# Brandon_PCB_DogTag.net
KiCad netlist of a schematic drawn in Altium Designer
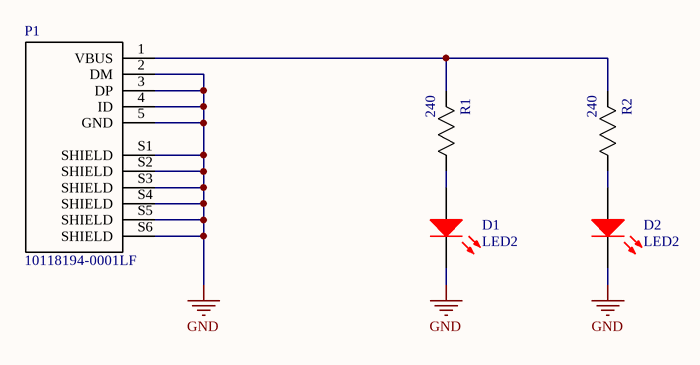
[diagram p0: Brandon PCB DogTag.SchDoc]

(export (version "E")
  (design (tool "Eeschema 10.0.6"))
  (components
    (comp (ref "D1")
      (value "LED2")
      (footprint "3.2X1.6X1.1")
      (description "Typical RED, GREEN, YELLOW, AMBER GaAs LED")
      (libsource (lib "AltiumLibraries") (part "LED RED SMD"))
    )
    (comp (ref "D2")
      (value "LED2")
      (footprint "3.2X1.6X1.1")
      (description "Typical RED, GREEN, YELLOW, AMBER GaAs LED")
      (libsource (lib "AltiumLibraries") (part "LED RED SMD"))
    )
    (comp (ref "P1")
      (value "10118194-0001LF")
      (footprint "USB Micro B Receptacle")
      (description "USB - micro B USB 2.0 Receptacle Connector 5 Position Surface Mount, Right Angle; Through Hole")
      (fields (field (name "MF") "Amphenol ICC (FCI)"))
      (libsource (lib "AltiumLibraries") (part "USB Micro B Receptacle"))
    )
    (comp (ref "R1")
      (value "240")
      (footprint "0805")
      (description "RES SMD 240 OHM 5% 1/8W 0805")
      (fields (field (name "TOLERANCE") "5%"))
      (libsource (lib "AltiumLibraries") (part "RES 240.0 1/8W"))
    )
    (comp (ref "R2")
      (value "240")
      (footprint "0805")
      (description "RES SMD 240 OHM 5% 1/8W 0805")
      (fields (field (name "TOLERANCE") "5%"))
      (libsource (lib "AltiumLibraries") (part "RES 240.0 1/8W"))
    )
  )
  (nets
    (net (code "1") (name "GND") (class "Default")
      (node (ref "D1") (pin "2") (pinfunction "K_2") (pintype "passive"))
      (node (ref "D2") (pin "2") (pinfunction "K_2") (pintype "passive"))
      (node (ref "P1") (pin "2") (pinfunction "DM_2") (pintype "passive"))
      (node (ref "P1") (pin "3") (pinfunction "DP_3") (pintype "passive"))
      (node (ref "P1") (pin "4") (pinfunction "ID_4") (pintype "passive"))
      (node (ref "P1") (pin "5") (pinfunction "GND_5") (pintype "passive"))
      (node (ref "P1") (pin "S1") (pinfunction "SHIELD_S1") (pintype "passive"))
      (node (ref "P1") (pin "S2") (pinfunction "SHIELD_S2") (pintype "passive"))
      (node (ref "P1") (pin "S3") (pinfunction "SHIELD_S3") (pintype "passive"))
      (node (ref "P1") (pin "S4") (pinfunction "SHIELD_S4") (pintype "passive"))
      (node (ref "P1") (pin "S5") (pinfunction "SHIELD_S5") (pintype "passive"))
      (node (ref "P1") (pin "S6") (pinfunction "SHIELD_S6") (pintype "passive"))
    )
    (net (code "2") (name "Net-(D1-A)") (class "Default")
      (node (ref "D1") (pin "1") (pinfunction "A_1") (pintype "passive"))
      (node (ref "R1") (pin "1") (pinfunction "R1_1") (pintype "passive"))
    )
    (net (code "3") (name "Net-(D2-A)") (class "Default")
      (node (ref "D2") (pin "1") (pinfunction "A_1") (pintype "passive"))
      (node (ref "R2") (pin "1") (pinfunction "R1_1") (pintype "passive"))
    )
    (net (code "4") (name "Net-(P1-VBUS)") (class "Default")
      (node (ref "P1") (pin "1") (pinfunction "VBUS_1") (pintype "passive"))
      (node (ref "R1") (pin "2") (pinfunction "R2_2") (pintype "passive"))
      (node (ref "R2") (pin "2") (pinfunction "R2_2") (pintype "passive"))
    )
  )
)
